# overall_schematic.net
KiCad netlist of a schematic drawn in EAGLE
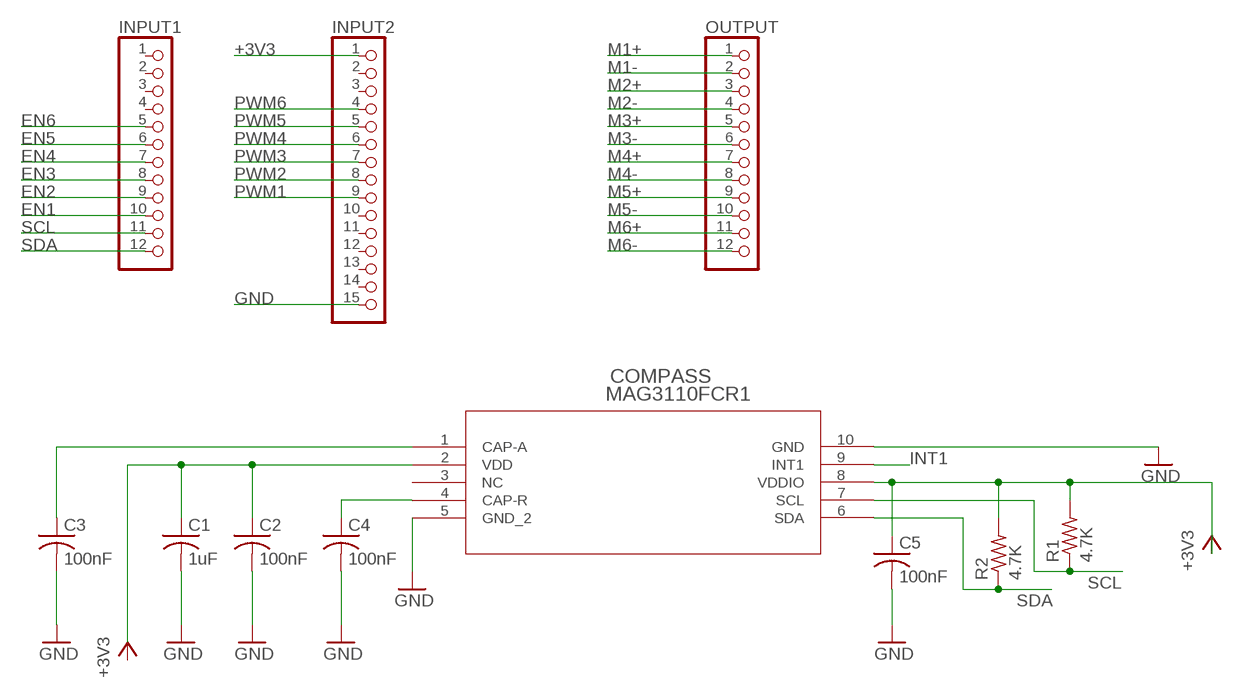
[diagram p0: schematic, sheet 1]
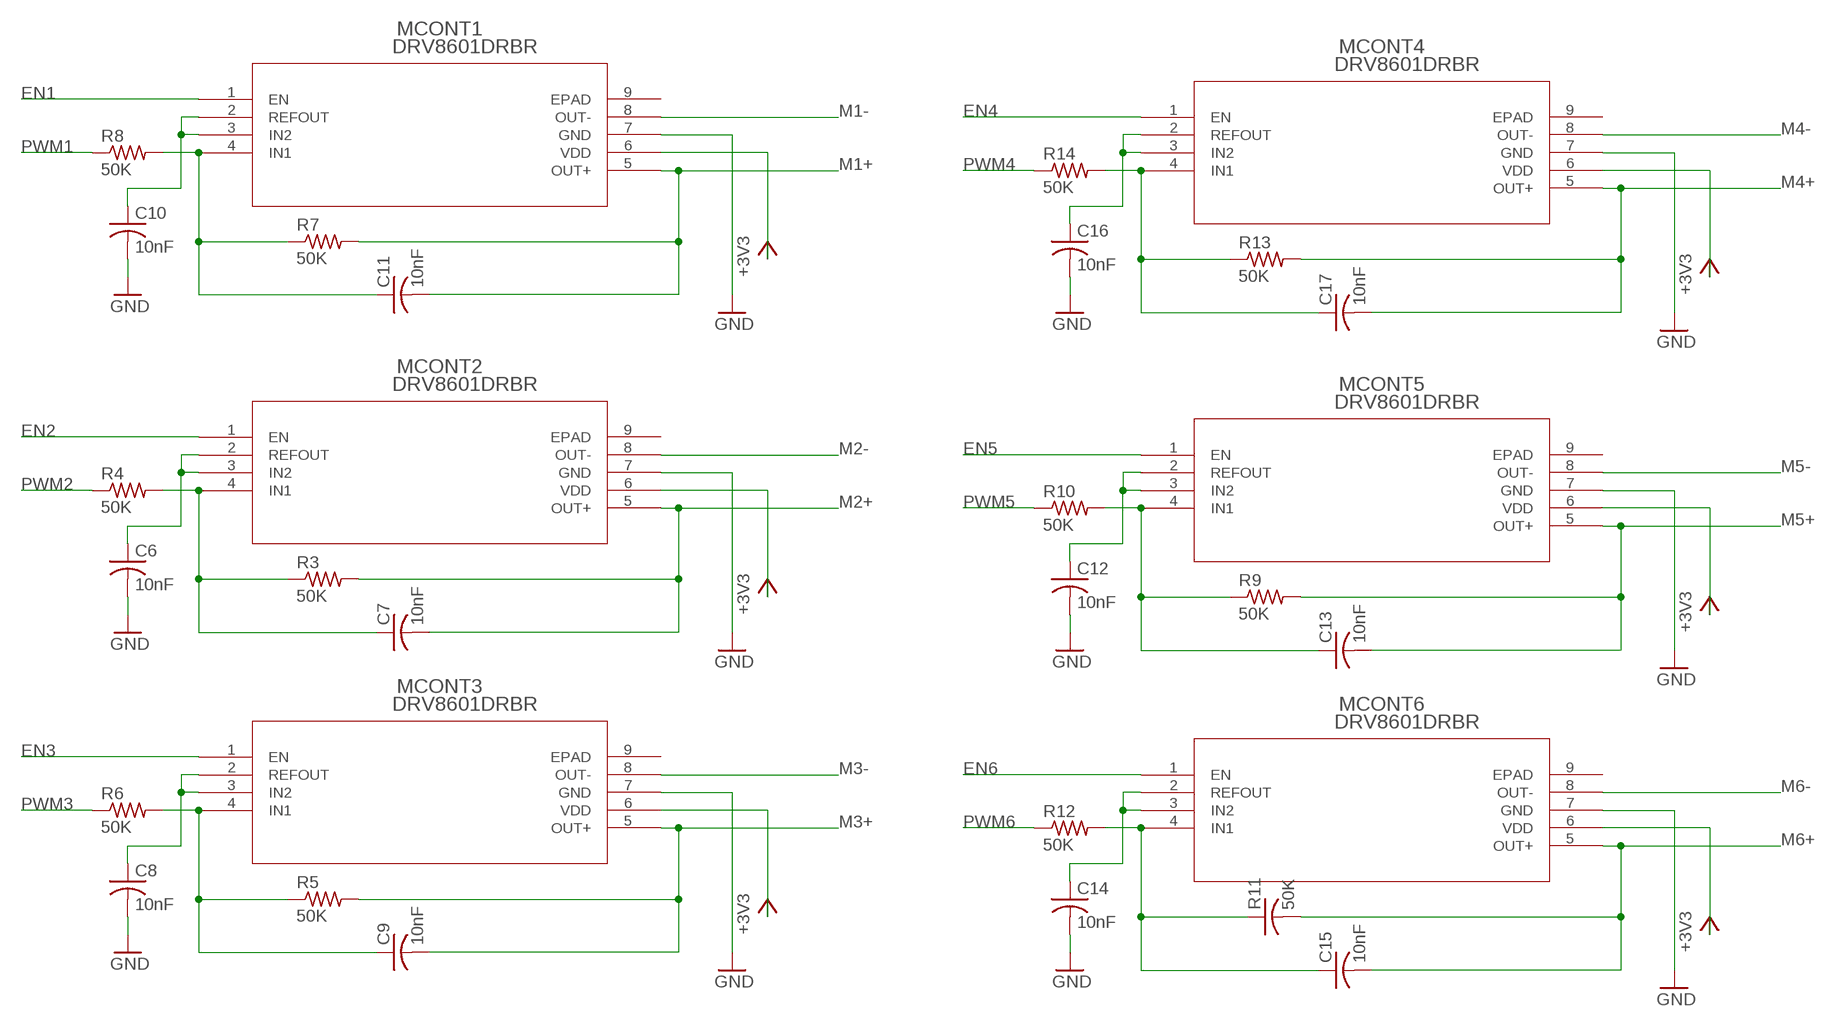
[diagram p1: schematic, sheet 2]

(export (version "E")
  (design (tool "Eeschema 10.0.6"))
  (components
    (comp (ref "C1")
      (value "1uF")
      (footprint "eagle-import:C0603")
      (libsource (lib "eagle-import") (part "C-USC0603"))
    )
    (comp (ref "C2")
      (value "100nF")
      (footprint "eagle-import:C0603")
      (libsource (lib "eagle-import") (part "C-USC0603"))
    )
    (comp (ref "C3")
      (value "100nF")
      (footprint "eagle-import:C0603")
      (libsource (lib "eagle-import") (part "C-USC0603"))
    )
    (comp (ref "C4")
      (value "100nF")
      (footprint "eagle-import:C0603")
      (libsource (lib "eagle-import") (part "C-USC0603"))
    )
    (comp (ref "C5")
      (value "100nF")
      (footprint "eagle-import:C0603")
      (libsource (lib "eagle-import") (part "C-USC0603"))
    )
    (comp (ref "COMPASS")
      (value "MAG3110FCR1")
      (footprint "eagle-import:DFN10")
      (fields
        (field (name "MANUFACTURER_PART_NUMBER") "mag3110fcr1")
        (field (name "COPYRIGHT") "Copyright C 2015 Accelerated Designs. All rights reserved")
      )
      (libsource (lib "eagle-import") (part "MAG3110FCR1"))
    )
    (comp (ref "INPUT1")
      (value "PINHD-1X12-CB")
      (footprint "eagle-import:1X12-CB")
      (libsource (lib "eagle-import") (part "PINHD-1X12-CB"))
    )
    (comp (ref "INPUT2")
      (value "PINHD-1X15-CB")
      (footprint "eagle-import:1X15-CB")
      (libsource (lib "eagle-import") (part "PINHD-1X15-CB"))
    )
    (comp (ref "OUTPUT")
      (value "PINHD-1X12-CB")
      (footprint "eagle-import:1X12-CB")
      (libsource (lib "eagle-import") (part "PINHD-1X12-CB"))
    )
    (comp (ref "R1")
      (value "4.7K")
      (footprint "eagle-import:R0603")
      (libsource (lib "eagle-import") (part "R-US_R0603"))
    )
    (comp (ref "R2")
      (value "4.7K")
      (footprint "eagle-import:R0603")
      (libsource (lib "eagle-import") (part "R-US_R0603"))
    )
    (comp (ref "C6")
      (value "10nF")
      (footprint "eagle-import:C0603")
      (libsource (lib "eagle-import") (part "C-USC0603"))
    )
    (comp (ref "C7")
      (value "10nF")
      (footprint "eagle-import:C0603")
      (libsource (lib "eagle-import") (part "C-USC0603"))
    )
    (comp (ref "C8")
      (value "10nF")
      (footprint "eagle-import:C0603")
      (libsource (lib "eagle-import") (part "C-USC0603"))
    )
    (comp (ref "C9")
      (value "10nF")
      (footprint "eagle-import:C0603")
      (libsource (lib "eagle-import") (part "C-USC0603"))
    )
    (comp (ref "C10")
      (value "10nF")
      (footprint "eagle-import:C0603")
      (libsource (lib "eagle-import") (part "C-USC0603"))
    )
    (comp (ref "C11")
      (value "10nF")
      (footprint "eagle-import:C0603")
      (libsource (lib "eagle-import") (part "C-USC0603"))
    )
    (comp (ref "C12")
      (value "10nF")
      (footprint "eagle-import:C0603")
      (libsource (lib "eagle-import") (part "C-USC0603"))
    )
    (comp (ref "C13")
      (value "10nF")
      (footprint "eagle-import:C0603")
      (libsource (lib "eagle-import") (part "C-USC0603"))
    )
    (comp (ref "C14")
      (value "10nF")
      (footprint "eagle-import:C0603")
      (libsource (lib "eagle-import") (part "C-USC0603"))
    )
    (comp (ref "C15")
      (value "10nF")
      (footprint "eagle-import:C0603")
      (libsource (lib "eagle-import") (part "C-USC0603"))
    )
    (comp (ref "C16")
      (value "10nF")
      (footprint "eagle-import:C0603")
      (libsource (lib "eagle-import") (part "C-USC0603"))
    )
    (comp (ref "C17")
      (value "10nF")
      (footprint "eagle-import:C0603")
      (libsource (lib "eagle-import") (part "C-USC0603"))
    )
    (comp (ref "MCONT1")
      (value "DRV8601DRBR")
      (footprint "eagle-import:DRB8_1P75X1P5")
      (fields
        (field (name "GENERIC_PART_NUMBER") "DRV8601")
        (field (name "MANUFACTURER") "Texas Instruments")
        (field (name "COPYRIGHT") "Copyright C 2015 Accelerated Designs. All rights reserved")
      )
      (libsource (lib "eagle-import") (part "DRV8601DRBR"))
    )
    (comp (ref "MCONT2")
      (value "DRV8601DRBR")
      (footprint "eagle-import:DRB8_1P75X1P5")
      (fields
        (field (name "GENERIC_PART_NUMBER") "DRV8601")
        (field (name "MANUFACTURER") "Texas Instruments")
        (field (name "COPYRIGHT") "Copyright C 2015 Accelerated Designs. All rights reserved")
      )
      (libsource (lib "eagle-import") (part "DRV8601DRBR"))
    )
    (comp (ref "MCONT3")
      (value "DRV8601DRBR")
      (footprint "eagle-import:DRB8_1P75X1P5")
      (fields
        (field (name "GENERIC_PART_NUMBER") "DRV8601")
        (field (name "MANUFACTURER") "Texas Instruments")
        (field (name "COPYRIGHT") "Copyright C 2015 Accelerated Designs. All rights reserved")
      )
      (libsource (lib "eagle-import") (part "DRV8601DRBR"))
    )
    (comp (ref "MCONT4")
      (value "DRV8601DRBR")
      (footprint "eagle-import:DRB8_1P75X1P5")
      (fields
        (field (name "GENERIC_PART_NUMBER") "DRV8601")
        (field (name "MANUFACTURER") "Texas Instruments")
        (field (name "COPYRIGHT") "Copyright C 2015 Accelerated Designs. All rights reserved")
      )
      (libsource (lib "eagle-import") (part "DRV8601DRBR"))
    )
    (comp (ref "MCONT5")
      (value "DRV8601DRBR")
      (footprint "eagle-import:DRB8_1P75X1P5")
      (fields
        (field (name "GENERIC_PART_NUMBER") "DRV8601")
        (field (name "MANUFACTURER") "Texas Instruments")
        (field (name "COPYRIGHT") "Copyright C 2015 Accelerated Designs. All rights reserved")
      )
      (libsource (lib "eagle-import") (part "DRV8601DRBR"))
    )
    (comp (ref "MCONT6")
      (value "DRV8601DRBR")
      (footprint "eagle-import:DRB8_1P75X1P5")
      (fields
        (field (name "GENERIC_PART_NUMBER") "DRV8601")
        (field (name "MANUFACTURER") "Texas Instruments")
        (field (name "COPYRIGHT") "Copyright C 2015 Accelerated Designs. All rights reserved")
      )
      (libsource (lib "eagle-import") (part "DRV8601DRBR"))
    )
    (comp (ref "R3")
      (value "50K")
      (footprint "eagle-import:R0603")
      (libsource (lib "eagle-import") (part "R-US_R0603"))
    )
    (comp (ref "R4")
      (value "50K")
      (footprint "eagle-import:R0603")
      (libsource (lib "eagle-import") (part "R-US_R0603"))
    )
    (comp (ref "R5")
      (value "50K")
      (footprint "eagle-import:R0603")
      (libsource (lib "eagle-import") (part "R-US_R0603"))
    )
    (comp (ref "R6")
      (value "50K")
      (footprint "eagle-import:R0603")
      (libsource (lib "eagle-import") (part "R-US_R0603"))
    )
    (comp (ref "R7")
      (value "50K")
      (footprint "eagle-import:R0603")
      (libsource (lib "eagle-import") (part "R-US_R0603"))
    )
    (comp (ref "R8")
      (value "50K")
      (footprint "eagle-import:R0603")
      (libsource (lib "eagle-import") (part "R-US_R0603"))
    )
    (comp (ref "R9")
      (value "50K")
      (footprint "eagle-import:R0603")
      (libsource (lib "eagle-import") (part "R-US_R0603"))
    )
    (comp (ref "R10")
      (value "50K")
      (footprint "eagle-import:R0603")
      (libsource (lib "eagle-import") (part "R-US_R0603"))
    )
    (comp (ref "R11")
      (value "50K")
      (footprint "eagle-import:C0603")
      (libsource (lib "eagle-import") (part "C-USC0603"))
    )
    (comp (ref "R12")
      (value "50K")
      (footprint "eagle-import:R0603")
      (libsource (lib "eagle-import") (part "R-US_R0603"))
    )
    (comp (ref "R13")
      (value "50K")
      (footprint "eagle-import:R0603")
      (libsource (lib "eagle-import") (part "R-US_R0603"))
    )
    (comp (ref "R14")
      (value "50K")
      (footprint "eagle-import:R0603")
      (libsource (lib "eagle-import") (part "R-US_R0603"))
    )
  )
  (nets
    (net (code "1") (name "+3V3") (class "Default")
      (node (ref "C5") (pin "1") (pinfunction "1_1") (pintype "passive"))
      (node (ref "COMPASS") (pin "8") (pinfunction "VDDIO_8") (pintype "power_in"))
      (node (ref "INPUT2") (pin "1") (pinfunction "1_1") (pintype "passive"))
      (node (ref "MCONT1") (pin "6") (pinfunction "VDD_6") (pintype "power_in"))
      (node (ref "MCONT2") (pin "6") (pinfunction "VDD_6") (pintype "power_in"))
      (node (ref "MCONT3") (pin "6") (pinfunction "VDD_6") (pintype "power_in"))
      (node (ref "MCONT4") (pin "6") (pinfunction "VDD_6") (pintype "power_in"))
      (node (ref "MCONT5") (pin "6") (pinfunction "VDD_6") (pintype "power_in"))
      (node (ref "MCONT6") (pin "6") (pinfunction "VDD_6") (pintype "power_in"))
      (node (ref "R1") (pin "2") (pinfunction "2_2") (pintype "passive"))
      (node (ref "R2") (pin "2") (pinfunction "2_2") (pintype "passive"))
    )
    (net (code "2") (name "EN1") (class "Default")
      (node (ref "INPUT1") (pin "10") (pinfunction "10_10") (pintype "passive"))
      (node (ref "MCONT1") (pin "1") (pinfunction "EN_1") (pintype "input"))
    )
    (net (code "3") (name "EN2") (class "Default")
      (node (ref "INPUT1") (pin "9") (pinfunction "9_9") (pintype "passive"))
      (node (ref "MCONT2") (pin "1") (pinfunction "EN_1") (pintype "input"))
    )
    (net (code "4") (name "EN3") (class "Default")
      (node (ref "INPUT1") (pin "8") (pinfunction "8_8") (pintype "passive"))
      (node (ref "MCONT3") (pin "1") (pinfunction "EN_1") (pintype "input"))
    )
    (net (code "5") (name "EN4") (class "Default")
      (node (ref "INPUT1") (pin "7") (pinfunction "7_7") (pintype "passive"))
      (node (ref "MCONT4") (pin "1") (pinfunction "EN_1") (pintype "input"))
    )
    (net (code "6") (name "EN5") (class "Default")
      (node (ref "INPUT1") (pin "6") (pinfunction "6_6") (pintype "passive"))
      (node (ref "MCONT5") (pin "1") (pinfunction "EN_1") (pintype "input"))
    )
    (net (code "7") (name "EN6") (class "Default")
      (node (ref "INPUT1") (pin "5") (pinfunction "5_5") (pintype "passive"))
      (node (ref "MCONT6") (pin "1") (pinfunction "EN_1") (pintype "input"))
    )
    (net (code "8") (name "GND") (class "Default")
      (node (ref "C1") (pin "2") (pinfunction "2_2") (pintype "passive"))
      (node (ref "C10") (pin "2") (pinfunction "2_2") (pintype "passive"))
      (node (ref "C12") (pin "2") (pinfunction "2_2") (pintype "passive"))
      (node (ref "C14") (pin "2") (pinfunction "2_2") (pintype "passive"))
      (node (ref "C16") (pin "2") (pinfunction "2_2") (pintype "passive"))
      (node (ref "C2") (pin "2") (pinfunction "2_2") (pintype "passive"))
      (node (ref "C3") (pin "2") (pinfunction "2_2") (pintype "passive"))
      (node (ref "C4") (pin "2") (pinfunction "2_2") (pintype "passive"))
      (node (ref "C5") (pin "2") (pinfunction "2_2") (pintype "passive"))
      (node (ref "C6") (pin "2") (pinfunction "2_2") (pintype "passive"))
      (node (ref "C8") (pin "2") (pinfunction "2_2") (pintype "passive"))
      (node (ref "COMPASS") (pin "10") (pinfunction "GND_10") (pintype "power_in"))
      (node (ref "COMPASS") (pin "5") (pinfunction "GND_2_5") (pintype "power_in"))
      (node (ref "INPUT2") (pin "15") (pinfunction "15_15") (pintype "passive"))
      (node (ref "MCONT1") (pin "7") (pinfunction "GND_7") (pintype "power_in"))
      (node (ref "MCONT2") (pin "7") (pinfunction "GND_7") (pintype "power_in"))
      (node (ref "MCONT3") (pin "7") (pinfunction "GND_7") (pintype "power_in"))
      (node (ref "MCONT4") (pin "7") (pinfunction "GND_7") (pintype "power_in"))
      (node (ref "MCONT5") (pin "7") (pinfunction "GND_7") (pintype "power_in"))
      (node (ref "MCONT6") (pin "7") (pinfunction "GND_7") (pintype "power_in"))
    )
    (net (code "9") (name "INT1") (class "Default")
      (node (ref "COMPASS") (pin "9") (pinfunction "INT1_9") (pintype "passive"))
    )
    (net (code "10") (name "M1+") (class "Default")
      (node (ref "C11") (pin "2") (pinfunction "2_2") (pintype "passive"))
      (node (ref "MCONT1") (pin "5") (pinfunction "OUT+_5") (pintype "output"))
      (node (ref "OUTPUT") (pin "1") (pinfunction "1_1") (pintype "passive"))
      (node (ref "R7") (pin "2") (pinfunction "2_2") (pintype "passive"))
    )
    (net (code "11") (name "M1-") (class "Default")
      (node (ref "MCONT1") (pin "8") (pinfunction "OUT-_8") (pintype "output"))
      (node (ref "OUTPUT") (pin "2") (pinfunction "2_2") (pintype "passive"))
    )
    (net (code "12") (name "M2+") (class "Default")
      (node (ref "C7") (pin "2") (pinfunction "2_2") (pintype "passive"))
      (node (ref "MCONT2") (pin "5") (pinfunction "OUT+_5") (pintype "output"))
      (node (ref "OUTPUT") (pin "3") (pinfunction "3_3") (pintype "passive"))
      (node (ref "R3") (pin "2") (pinfunction "2_2") (pintype "passive"))
    )
    (net (code "13") (name "M2-") (class "Default")
      (node (ref "MCONT2") (pin "8") (pinfunction "OUT-_8") (pintype "output"))
      (node (ref "OUTPUT") (pin "4") (pinfunction "4_4") (pintype "passive"))
    )
    (net (code "14") (name "M3+") (class "Default")
      (node (ref "C9") (pin "2") (pinfunction "2_2") (pintype "passive"))
      (node (ref "MCONT3") (pin "5") (pinfunction "OUT+_5") (pintype "output"))
      (node (ref "OUTPUT") (pin "5") (pinfunction "5_5") (pintype "passive"))
      (node (ref "R5") (pin "2") (pinfunction "2_2") (pintype "passive"))
    )
    (net (code "15") (name "M3-") (class "Default")
      (node (ref "MCONT3") (pin "8") (pinfunction "OUT-_8") (pintype "output"))
      (node (ref "OUTPUT") (pin "6") (pinfunction "6_6") (pintype "passive"))
    )
    (net (code "16") (name "M4+") (class "Default")
      (node (ref "C17") (pin "2") (pinfunction "2_2") (pintype "passive"))
      (node (ref "MCONT4") (pin "5") (pinfunction "OUT+_5") (pintype "output"))
      (node (ref "OUTPUT") (pin "7") (pinfunction "7_7") (pintype "passive"))
      (node (ref "R13") (pin "2") (pinfunction "2_2") (pintype "passive"))
    )
    (net (code "17") (name "M4-") (class "Default")
      (node (ref "MCONT4") (pin "8") (pinfunction "OUT-_8") (pintype "output"))
      (node (ref "OUTPUT") (pin "8") (pinfunction "8_8") (pintype "passive"))
    )
    (net (code "18") (name "M5+") (class "Default")
      (node (ref "C13") (pin "2") (pinfunction "2_2") (pintype "passive"))
      (node (ref "MCONT5") (pin "5") (pinfunction "OUT+_5") (pintype "output"))
      (node (ref "OUTPUT") (pin "9") (pinfunction "9_9") (pintype "passive"))
      (node (ref "R9") (pin "2") (pinfunction "2_2") (pintype "passive"))
    )
    (net (code "19") (name "M5-") (class "Default")
      (node (ref "MCONT5") (pin "8") (pinfunction "OUT-_8") (pintype "output"))
      (node (ref "OUTPUT") (pin "10") (pinfunction "10_10") (pintype "passive"))
    )
    (net (code "20") (name "M6+") (class "Default")
      (node (ref "C15") (pin "2") (pinfunction "2_2") (pintype "passive"))
      (node (ref "MCONT6") (pin "5") (pinfunction "OUT+_5") (pintype "output"))
      (node (ref "OUTPUT") (pin "11") (pinfunction "11_11") (pintype "passive"))
      (node (ref "R11") (pin "2") (pinfunction "2_2") (pintype "passive"))
    )
    (net (code "21") (name "M6-") (class "Default")
      (node (ref "MCONT6") (pin "8") (pinfunction "OUT-_8") (pintype "output"))
      (node (ref "OUTPUT") (pin "12") (pinfunction "12_12") (pintype "passive"))
    )
    (net (code "22") (name "Net-(COMPASS-CAP-A)") (class "Default")
      (node (ref "C3") (pin "1") (pinfunction "1_1") (pintype "passive"))
      (node (ref "COMPASS") (pin "1") (pinfunction "CAP-A_1") (pintype "passive"))
    )
    (net (code "23") (name "Net-(COMPASS-CAP-R)") (class "Default")
      (node (ref "C4") (pin "1") (pinfunction "1_1") (pintype "passive"))
      (node (ref "COMPASS") (pin "4") (pinfunction "CAP-R_4") (pintype "passive"))
    )
    (net (code "24") (name "Net-(COMPASS-VDD)") (class "Default")
      (node (ref "C1") (pin "1") (pinfunction "1_1") (pintype "passive"))
      (node (ref "C2") (pin "1") (pinfunction "1_1") (pintype "passive"))
      (node (ref "COMPASS") (pin "2") (pinfunction "VDD_2") (pintype "power_in"))
    )
    (net (code "25") (name "Net-(MCONT1-IN1)") (class "Default")
      (node (ref "C11") (pin "1") (pinfunction "1_1") (pintype "passive"))
      (node (ref "MCONT1") (pin "4") (pinfunction "IN1_4") (pintype "input"))
      (node (ref "R7") (pin "1") (pinfunction "1_1") (pintype "passive"))
      (node (ref "R8") (pin "2") (pinfunction "2_2") (pintype "passive"))
    )
    (net (code "26") (name "Net-(MCONT1-IN2)") (class "Default")
      (node (ref "C10") (pin "1") (pinfunction "1_1") (pintype "passive"))
      (node (ref "MCONT1") (pin "2") (pinfunction "REFOUT_2") (pintype "output"))
      (node (ref "MCONT1") (pin "3") (pinfunction "IN2_3") (pintype "input"))
    )
    (net (code "27") (name "Net-(MCONT2-IN1)") (class "Default")
      (node (ref "C7") (pin "1") (pinfunction "1_1") (pintype "passive"))
      (node (ref "MCONT2") (pin "4") (pinfunction "IN1_4") (pintype "input"))
      (node (ref "R3") (pin "1") (pinfunction "1_1") (pintype "passive"))
      (node (ref "R4") (pin "2") (pinfunction "2_2") (pintype "passive"))
    )
    (net (code "28") (name "Net-(MCONT2-IN2)") (class "Default")
      (node (ref "C6") (pin "1") (pinfunction "1_1") (pintype "passive"))
      (node (ref "MCONT2") (pin "2") (pinfunction "REFOUT_2") (pintype "output"))
      (node (ref "MCONT2") (pin "3") (pinfunction "IN2_3") (pintype "input"))
    )
    (net (code "29") (name "Net-(MCONT3-IN1)") (class "Default")
      (node (ref "C9") (pin "1") (pinfunction "1_1") (pintype "passive"))
      (node (ref "MCONT3") (pin "4") (pinfunction "IN1_4") (pintype "input"))
      (node (ref "R5") (pin "1") (pinfunction "1_1") (pintype "passive"))
      (node (ref "R6") (pin "2") (pinfunction "2_2") (pintype "passive"))
    )
    (net (code "30") (name "Net-(MCONT3-IN2)") (class "Default")
      (node (ref "C8") (pin "1") (pinfunction "1_1") (pintype "passive"))
      (node (ref "MCONT3") (pin "2") (pinfunction "REFOUT_2") (pintype "output"))
      (node (ref "MCONT3") (pin "3") (pinfunction "IN2_3") (pintype "input"))
    )
    (net (code "31") (name "Net-(MCONT4-IN1)") (class "Default")
      (node (ref "C17") (pin "1") (pinfunction "1_1") (pintype "passive"))
      (node (ref "MCONT4") (pin "4") (pinfunction "IN1_4") (pintype "input"))
      (node (ref "R13") (pin "1") (pinfunction "1_1") (pintype "passive"))
      (node (ref "R14") (pin "2") (pinfunction "2_2") (pintype "passive"))
    )
    (net (code "32") (name "Net-(MCONT4-IN2)") (class "Default")
      (node (ref "C16") (pin "1") (pinfunction "1_1") (pintype "passive"))
      (node (ref "MCONT4") (pin "2") (pinfunction "REFOUT_2") (pintype "output"))
      (node (ref "MCONT4") (pin "3") (pinfunction "IN2_3") (pintype "input"))
    )
    (net (code "33") (name "Net-(MCONT5-IN1)") (class "Default")
      (node (ref "C13") (pin "1") (pinfunction "1_1") (pintype "passive"))
      (node (ref "MCONT5") (pin "4") (pinfunction "IN1_4") (pintype "input"))
      (node (ref "R10") (pin "2") (pinfunction "2_2") (pintype "passive"))
      (node (ref "R9") (pin "1") (pinfunction "1_1") (pintype "passive"))
    )
    (net (code "34") (name "Net-(MCONT5-IN2)") (class "Default")
      (node (ref "C12") (pin "1") (pinfunction "1_1") (pintype "passive"))
      (node (ref "MCONT5") (pin "2") (pinfunction "REFOUT_2") (pintype "output"))
      (node (ref "MCONT5") (pin "3") (pinfunction "IN2_3") (pintype "input"))
    )
    (net (code "35") (name "Net-(MCONT6-IN1)") (class "Default")
      (node (ref "C15") (pin "1") (pinfunction "1_1") (pintype "passive"))
      (node (ref "MCONT6") (pin "4") (pinfunction "IN1_4") (pintype "input"))
      (node (ref "R11") (pin "1") (pinfunction "1_1") (pintype "passive"))
      (node (ref "R12") (pin "2") (pinfunction "2_2") (pintype "passive"))
    )
    (net (code "36") (name "Net-(MCONT6-IN2)") (class "Default")
      (node (ref "C14") (pin "1") (pinfunction "1_1") (pintype "passive"))
      (node (ref "MCONT6") (pin "2") (pinfunction "REFOUT_2") (pintype "output"))
      (node (ref "MCONT6") (pin "3") (pinfunction "IN2_3") (pintype "input"))
    )
    (net (code "37") (name "PWM1") (class "Default")
      (node (ref "INPUT2") (pin "9") (pinfunction "9_9") (pintype "passive"))
      (node (ref "R8") (pin "1") (pinfunction "1_1") (pintype "passive"))
    )
    (net (code "38") (name "PWM2") (class "Default")
      (node (ref "INPUT2") (pin "8") (pinfunction "8_8") (pintype "passive"))
      (node (ref "R4") (pin "1") (pinfunction "1_1") (pintype "passive"))
    )
    (net (code "39") (name "PWM3") (class "Default")
      (node (ref "INPUT2") (pin "7") (pinfunction "7_7") (pintype "passive"))
      (node (ref "R6") (pin "1") (pinfunction "1_1") (pintype "passive"))
    )
    (net (code "40") (name "PWM4") (class "Default")
      (node (ref "INPUT2") (pin "6") (pinfunction "6_6") (pintype "passive"))
      (node (ref "R14") (pin "1") (pinfunction "1_1") (pintype "passive"))
    )
    (net (code "41") (name "PWM5") (class "Default")
      (node (ref "INPUT2") (pin "5") (pinfunction "5_5") (pintype "passive"))
      (node (ref "R10") (pin "1") (pinfunction "1_1") (pintype "passive"))
    )
    (net (code "42") (name "PWM6") (class "Default")
      (node (ref "INPUT2") (pin "4") (pinfunction "4_4") (pintype "passive"))
      (node (ref "R12") (pin "1") (pinfunction "1_1") (pintype "passive"))
    )
    (net (code "43") (name "SCL") (class "Default")
      (node (ref "COMPASS") (pin "7") (pinfunction "SCL_7") (pintype "passive"))
      (node (ref "INPUT1") (pin "11") (pinfunction "11_11") (pintype "passive"))
      (node (ref "R1") (pin "1") (pinfunction "1_1") (pintype "passive"))
    )
    (net (code "44") (name "SDA") (class "Default")
      (node (ref "COMPASS") (pin "6") (pinfunction "SDA_6") (pintype "passive"))
      (node (ref "INPUT1") (pin "12") (pinfunction "12_12") (pintype "passive"))
      (node (ref "R2") (pin "1") (pinfunction "1_1") (pintype "passive"))
    )
    (net (code "45") (name "unconnected-(COMPASS-NC-Pad3)") (class "Default")
      (node (ref "COMPASS") (pin "3") (pinfunction "NC_3") (pintype "passive"))
    )
    (net (code "46") (name "unconnected-(INPUT1-Pad1)") (class "Default")
      (node (ref "INPUT1") (pin "1") (pinfunction "1_1") (pintype "passive"))
    )
    (net (code "47") (name "unconnected-(INPUT1-Pad2)") (class "Default")
      (node (ref "INPUT1") (pin "2") (pinfunction "2_2") (pintype "passive"))
    )
    (net (code "48") (name "unconnected-(INPUT1-Pad3)") (class "Default")
      (node (ref "INPUT1") (pin "3") (pinfunction "3_3") (pintype "passive"))
    )
    (net (code "49") (name "unconnected-(INPUT1-Pad4)") (class "Default")
      (node (ref "INPUT1") (pin "4") (pinfunction "4_4") (pintype "passive"))
    )
    (net (code "50") (name "unconnected-(INPUT2-Pad2)") (class "Default")
      (node (ref "INPUT2") (pin "2") (pinfunction "2_2") (pintype "passive"))
    )
    (net (code "51") (name "unconnected-(INPUT2-Pad3)") (class "Default")
      (node (ref "INPUT2") (pin "3") (pinfunction "3_3") (pintype "passive"))
    )
    (net (code "52") (name "unconnected-(INPUT2-Pad10)") (class "Default")
      (node (ref "INPUT2") (pin "10") (pinfunction "10_10") (pintype "passive"))
    )
    (net (code "53") (name "unconnected-(INPUT2-Pad11)") (class "Default")
      (node (ref "INPUT2") (pin "11") (pinfunction "11_11") (pintype "passive"))
    )
    (net (code "54") (name "unconnected-(INPUT2-Pad12)") (class "Default")
      (node (ref "INPUT2") (pin "12") (pinfunction "12_12") (pintype "passive"))
    )
    (net (code "55") (name "unconnected-(INPUT2-Pad13)") (class "Default")
      (node (ref "INPUT2") (pin "13") (pinfunction "13_13") (pintype "passive"))
    )
    (net (code "56") (name "unconnected-(INPUT2-Pad14)") (class "Default")
      (node (ref "INPUT2") (pin "14") (pinfunction "14_14") (pintype "passive"))
    )
    (net (code "57") (name "unconnected-(MCONT1-EPAD-Pad9)") (class "Default")
      (node (ref "MCONT1") (pin "9") (pinfunction "EPAD_9") (pintype "passive"))
    )
    (net (code "58") (name "unconnected-(MCONT2-EPAD-Pad9)") (class "Default")
      (node (ref "MCONT2") (pin "9") (pinfunction "EPAD_9") (pintype "passive"))
    )
    (net (code "59") (name "unconnected-(MCONT3-EPAD-Pad9)") (class "Default")
      (node (ref "MCONT3") (pin "9") (pinfunction "EPAD_9") (pintype "passive"))
    )
    (net (code "60") (name "unconnected-(MCONT4-EPAD-Pad9)") (class "Default")
      (node (ref "MCONT4") (pin "9") (pinfunction "EPAD_9") (pintype "passive"))
    )
    (net (code "61") (name "unconnected-(MCONT5-EPAD-Pad9)") (class "Default")
      (node (ref "MCONT5") (pin "9") (pinfunction "EPAD_9") (pintype "passive"))
    )
    (net (code "62") (name "unconnected-(MCONT6-EPAD-Pad9)") (class "Default")
      (node (ref "MCONT6") (pin "9") (pinfunction "EPAD_9") (pintype "passive"))
    )
  )
)
